# etna-sch-driver.net
KiCad netlist of a schematic drawn in Altium Designer
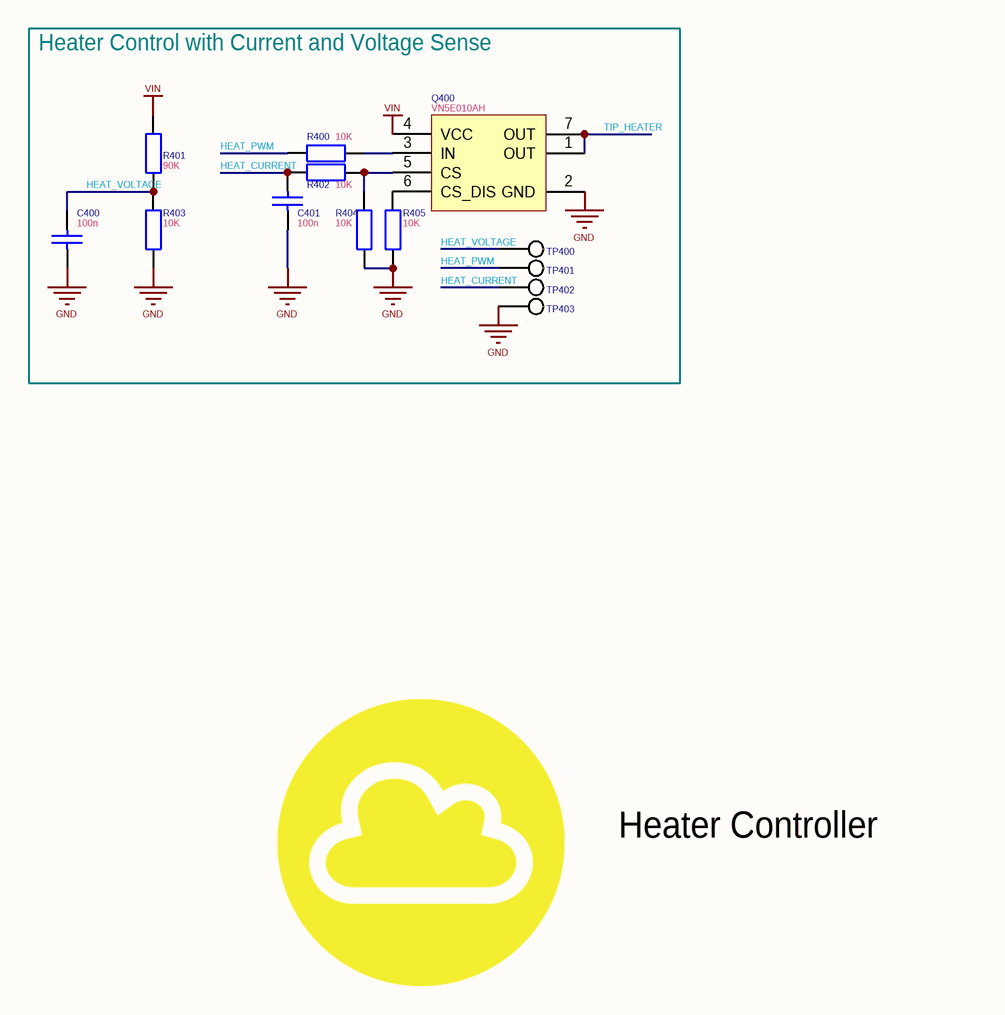
[diagram p0: etna-sch-driver.SchDoc]

(export (version "E")
  (design (tool "Eeschema 10.0.6"))
  (components
    (comp (ref "C400")
      (value "100n")
      (footprint "0402-capacitor")
      (description "Capacitor")
      (libsource (lib "illysky-components") (part "CAP"))
    )
    (comp (ref "C401")
      (value "100n")
      (footprint "0402-capacitor")
      (description "Capacitor")
      (libsource (lib "illysky-components") (part "CAP"))
    )
    (comp (ref "Q400")
      (value "VN5E010AH")
      (footprint "HPAK6")
      (description "10 m high-side driver with analog current sense  for automotive applications")
      (libsource (lib "illysky-components") (part "VN5E010AH"))
    )
    (comp (ref "R400")
      (value "10K")
      (footprint "0402-resistor")
      (description "Resistor")
      (libsource (lib "altium-import") (part "root_2_RES_"))
    )
    (comp (ref "R401")
      (value "90K")
      (footprint "0402-resistor")
      (description "Resistor")
      (libsource (lib "altium-import") (part "root_3_RES_"))
    )
    (comp (ref "R402")
      (value "10K")
      (footprint "0402-resistor")
      (description "Resistor")
      (libsource (lib "altium-import") (part "root_2_RES_"))
    )
    (comp (ref "R403")
      (value "10K")
      (footprint "0402-resistor")
      (description "Resistor")
      (libsource (lib "altium-import") (part "root_3_RES_"))
    )
    (comp (ref "R404")
      (value "10K")
      (footprint "0402-resistor")
      (description "Resistor")
      (libsource (lib "altium-import") (part "root_3_RES_"))
    )
    (comp (ref "R405")
      (value "10K")
      (footprint "0402-resistor")
      (description "Resistor")
      (libsource (lib "altium-import") (part "root_3_RES_"))
    )
    (comp (ref "TP400")
      (value "TP")
      (footprint "TESTPOINT")
      (libsource (lib "illysky-components") (part "TEST_POINT"))
    )
    (comp (ref "TP401")
      (value "TP")
      (footprint "TESTPOINT")
      (libsource (lib "illysky-components") (part "TEST_POINT"))
    )
    (comp (ref "TP402")
      (value "TP")
      (footprint "TESTPOINT")
      (libsource (lib "illysky-components") (part "TEST_POINT"))
    )
    (comp (ref "TP403")
      (value "TP")
      (footprint "TESTPOINT")
      (libsource (lib "illysky-components") (part "TEST_POINT"))
    )
  )
  (nets
    (net (code "1") (name "/HEAT_CURRENT") (class "Default")
      (node (ref "C401") (pin "2") (pinfunction "2_2") (pintype "passive"))
      (node (ref "R402") (pin "2") (pinfunction "2_2") (pintype "passive"))
      (node (ref "TP402") (pin "1") (pinfunction "GND_1") (pintype "passive"))
    )
    (net (code "2") (name "/HEAT_PWM") (class "Default")
      (node (ref "R400") (pin "2") (pinfunction "2_2") (pintype "passive"))
      (node (ref "TP401") (pin "1") (pinfunction "GND_1") (pintype "passive"))
    )
    (net (code "3") (name "/HEAT_VOLTAGE") (class "Default")
      (node (ref "C400") (pin "2") (pinfunction "2_2") (pintype "passive"))
      (node (ref "R401") (pin "2") (pinfunction "2_2") (pintype "passive"))
      (node (ref "R403") (pin "1") (pinfunction "1_1") (pintype "passive"))
      (node (ref "TP400") (pin "1") (pinfunction "GND_1") (pintype "passive"))
    )
    (net (code "4") (name "/TIP_HEATER") (class "Default")
      (node (ref "Q400") (pin "1") (pinfunction "OUT_1") (pintype "passive"))
      (node (ref "Q400") (pin "7") (pinfunction "OUT_7") (pintype "passive"))
    )
    (net (code "5") (name "GND") (class "Default")
      (node (ref "C400") (pin "1") (pinfunction "1_1") (pintype "passive"))
      (node (ref "C401") (pin "1") (pinfunction "1_1") (pintype "passive"))
      (node (ref "Q400") (pin "2") (pinfunction "GND_2") (pintype "passive"))
      (node (ref "R403") (pin "2") (pinfunction "2_2") (pintype "passive"))
      (node (ref "R404") (pin "2") (pinfunction "2_2") (pintype "passive"))
      (node (ref "R405") (pin "2") (pinfunction "2_2") (pintype "passive"))
      (node (ref "TP403") (pin "1") (pinfunction "GND_1") (pintype "passive"))
    )
    (net (code "6") (name "Net-(Q400-CS)") (class "Default")
      (node (ref "Q400") (pin "5") (pinfunction "CS_5") (pintype "passive"))
      (node (ref "R402") (pin "1") (pinfunction "1_1") (pintype "passive"))
      (node (ref "R404") (pin "1") (pinfunction "1_1") (pintype "passive"))
    )
    (net (code "7") (name "Net-(Q400-CS_DIS)") (class "Default")
      (node (ref "Q400") (pin "6") (pinfunction "CS_DIS_6") (pintype "passive"))
      (node (ref "R405") (pin "1") (pinfunction "1_1") (pintype "passive"))
    )
    (net (code "8") (name "Net-(Q400-IN)") (class "Default")
      (node (ref "Q400") (pin "3") (pinfunction "IN_3") (pintype "passive"))
      (node (ref "R400") (pin "1") (pinfunction "1_1") (pintype "passive"))
    )
    (net (code "9") (name "VIN") (class "Default")
      (node (ref "Q400") (pin "4") (pinfunction "VCC_4") (pintype "passive"))
      (node (ref "R401") (pin "1") (pinfunction "1_1") (pintype "passive"))
    )
  )
)
